# power_supply.net
KiCad netlist of a schematic drawn in EAGLE
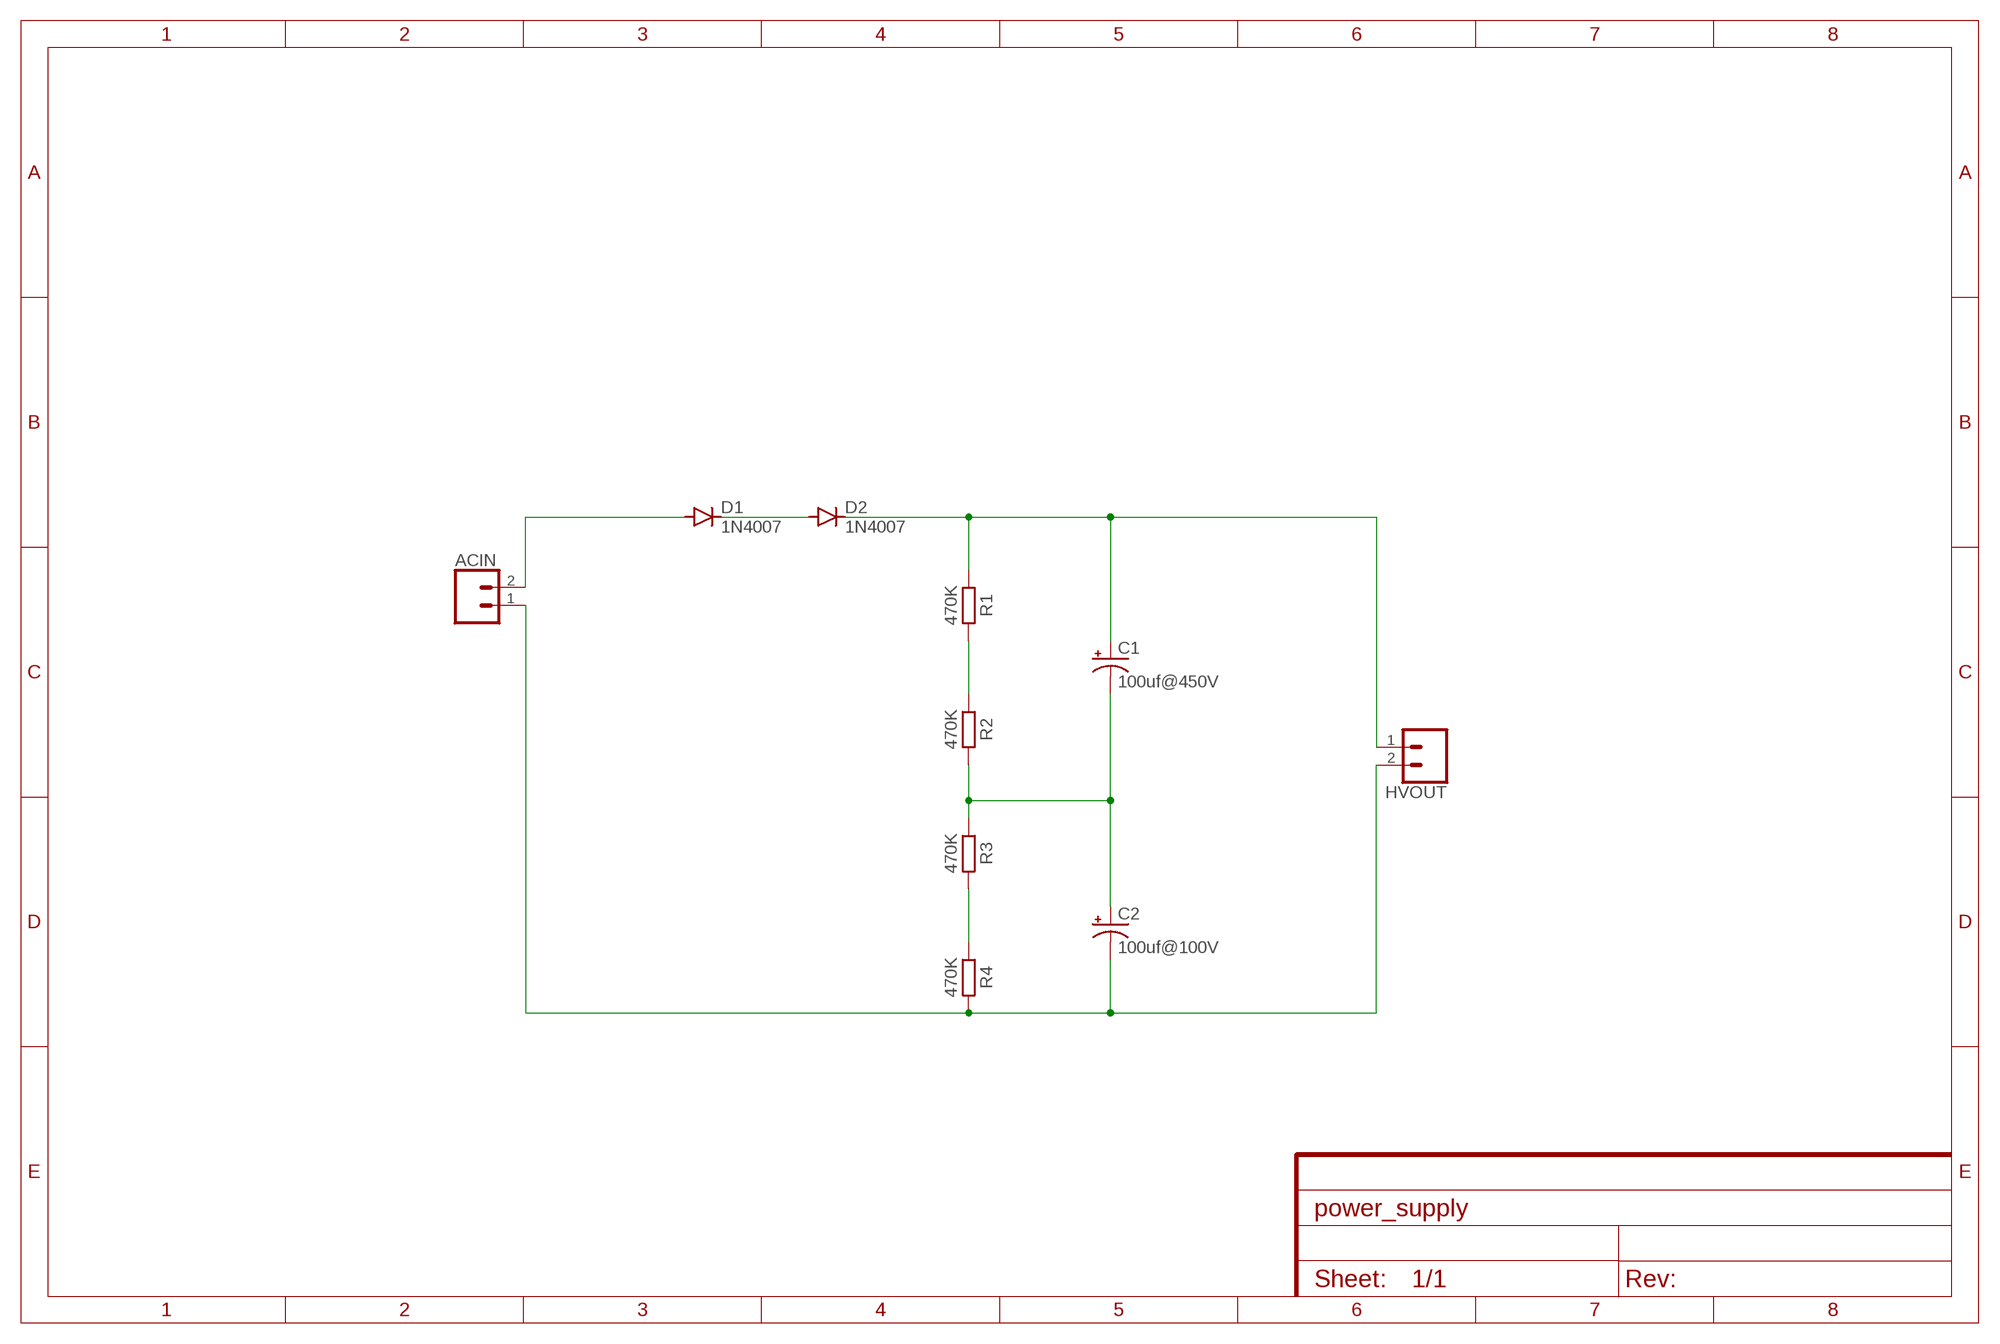
[diagram p0: schematic, sheet 1]

(export (version "E")
  (design (tool "Eeschema 10.0.6"))
  (components
    (comp (ref "ACIN")
      (value "CONN_02")
      (footprint "eagle-import:1X02")
      (libsource (lib "eagle-import") (part "CONN_02"))
    )
    (comp (ref "C1")
      (value "100uf@450V")
      (footprint "eagle-import:E5-6")
      (libsource (lib "eagle-import") (part "CPOL-USE5-6"))
    )
    (comp (ref "C2")
      (value "100uf@100V")
      (footprint "eagle-import:E5-6")
      (libsource (lib "eagle-import") (part "CPOL-USE5-6"))
    )
    (comp (ref "D1")
      (value "1N4007")
      (footprint "eagle-import:DO41-10")
      (libsource (lib "eagle-import") (part "1N4004"))
    )
    (comp (ref "D2")
      (value "1N4007")
      (footprint "eagle-import:DO41-10")
      (libsource (lib "eagle-import") (part "1N4004"))
    )
    (comp (ref "HVOUT")
      (value "CONN_02")
      (footprint "eagle-import:1X02")
      (libsource (lib "eagle-import") (part "CONN_02"))
    )
    (comp (ref "R1")
      (value "470K")
      (footprint "eagle-import:RESAD1176W63L850D250B")
      (libsource (lib "eagle-import") (part "RAXIAL-11.7MM-PITCH_"))
    )
    (comp (ref "R2")
      (value "470K")
      (footprint "eagle-import:RESAD1176W63L850D250B")
      (libsource (lib "eagle-import") (part "RAXIAL-11.7MM-PITCH_"))
    )
    (comp (ref "R3")
      (value "470K")
      (footprint "eagle-import:RESAD1176W63L850D250B")
      (libsource (lib "eagle-import") (part "RAXIAL-11.7MM-PITCH_"))
    )
    (comp (ref "R4")
      (value "470K")
      (footprint "eagle-import:RESAD1176W63L850D250B")
      (libsource (lib "eagle-import") (part "RAXIAL-11.7MM-PITCH_"))
    )
  )
  (nets
    (net (code "1") (name "Net-(ACIN-Pad1)") (class "Default")
      (node (ref "ACIN") (pin "1") (pinfunction "1_1") (pintype "passive"))
      (node (ref "C2") (pin "-") (pinfunction "-_-") (pintype "passive"))
      (node (ref "HVOUT") (pin "2") (pinfunction "2_2") (pintype "passive"))
      (node (ref "R4") (pin "2") (pinfunction "2_2") (pintype "passive"))
    )
    (net (code "2") (name "Net-(ACIN-Pad2)") (class "Default")
      (node (ref "ACIN") (pin "2") (pinfunction "2_2") (pintype "passive"))
      (node (ref "D1") (pin "A") (pinfunction "A_A") (pintype "passive"))
    )
    (net (code "3") (name "Net-(C1-Pad+)") (class "Default")
      (node (ref "C1") (pin "+") (pinfunction "+_+") (pintype "passive"))
      (node (ref "D2") (pin "C") (pinfunction "C_C") (pintype "passive"))
      (node (ref "HVOUT") (pin "1") (pinfunction "1_1") (pintype "passive"))
      (node (ref "R1") (pin "1") (pinfunction "1_1") (pintype "passive"))
    )
    (net (code "4") (name "Net-(C1-Pad-)") (class "Default")
      (node (ref "C1") (pin "-") (pinfunction "-_-") (pintype "passive"))
      (node (ref "C2") (pin "+") (pinfunction "+_+") (pintype "passive"))
      (node (ref "R2") (pin "2") (pinfunction "2_2") (pintype "passive"))
      (node (ref "R3") (pin "1") (pinfunction "1_1") (pintype "passive"))
    )
    (net (code "5") (name "Net-(D1-PadC)") (class "Default")
      (node (ref "D1") (pin "C") (pinfunction "C_C") (pintype "passive"))
      (node (ref "D2") (pin "A") (pinfunction "A_A") (pintype "passive"))
    )
    (net (code "6") (name "Net-(R1-Pad2)") (class "Default")
      (node (ref "R1") (pin "2") (pinfunction "2_2") (pintype "passive"))
      (node (ref "R2") (pin "1") (pinfunction "1_1") (pintype "passive"))
    )
    (net (code "7") (name "Net-(R3-Pad2)") (class "Default")
      (node (ref "R3") (pin "2") (pinfunction "2_2") (pintype "passive"))
      (node (ref "R4") (pin "1") (pinfunction "1_1") (pintype "passive"))
    )
  )
)
